# cyclo_no_flash.net
KiCad netlist of a schematic drawn in EAGLE
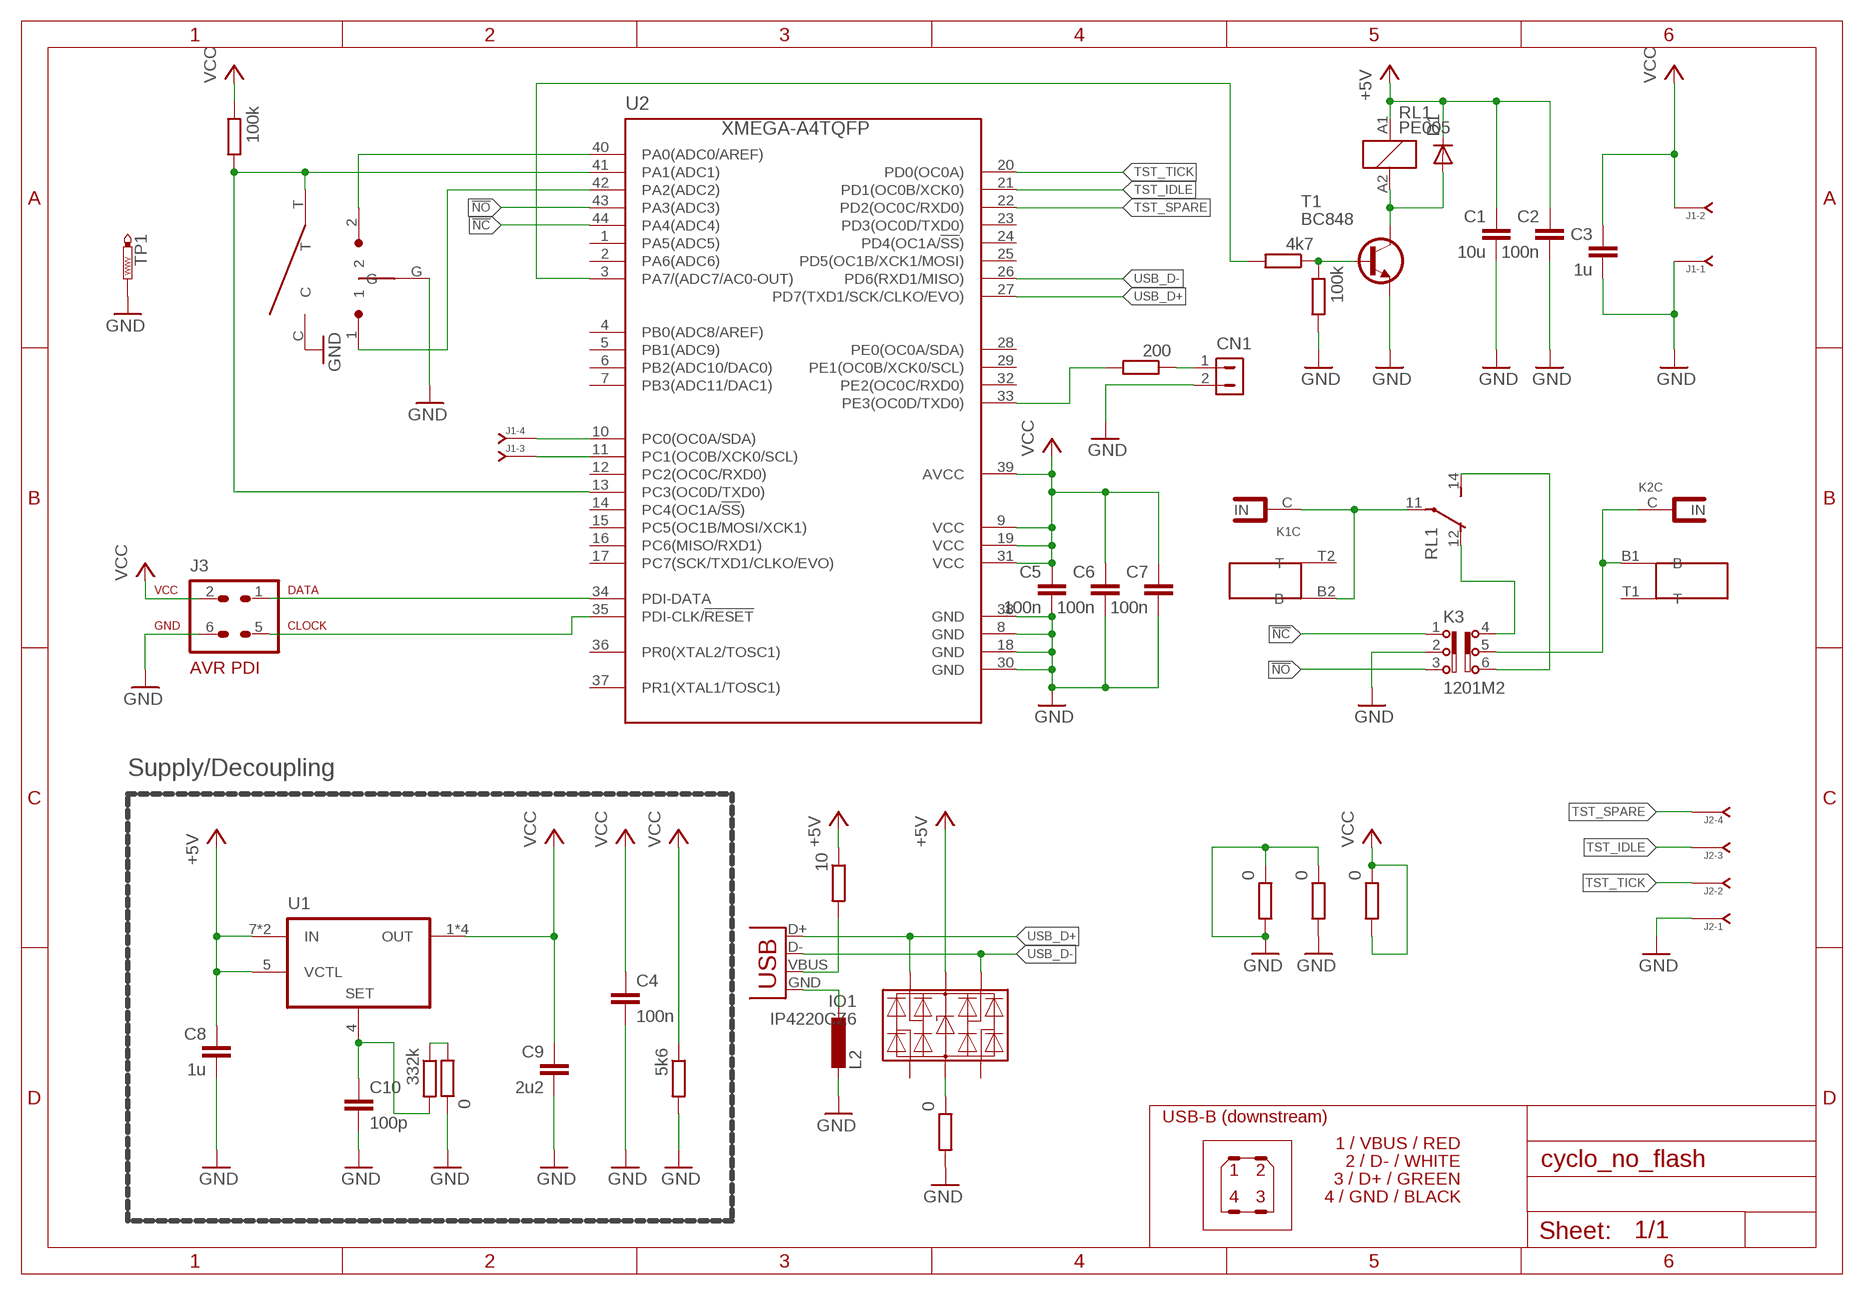
[diagram p0: schematic, sheet 1]

(export (version "E")
  (design (tool "Eeschema 10.0.6"))
  (components
    (comp (ref "C1")
      (value "10u")
      (footprint "eagle-import:C1210K")
      (libsource (lib "eagle-import") (part "C-EUC1210K"))
    )
    (comp (ref "C2")
      (value "100n")
      (footprint "eagle-import:C0603K")
      (libsource (lib "eagle-import") (part "C-EUC0603K"))
    )
    (comp (ref "C3")
      (value "1u")
      (footprint "eagle-import:C0603K")
      (libsource (lib "eagle-import") (part "C-EUC0603K"))
    )
    (comp (ref "C4")
      (value "100n")
      (footprint "eagle-import:C0603K")
      (libsource (lib "eagle-import") (part "C-EUC0603K"))
    )
    (comp (ref "C5")
      (value "100n")
      (footprint "eagle-import:C0603K")
      (libsource (lib "eagle-import") (part "C-EUC0603K"))
    )
    (comp (ref "C6")
      (value "100n")
      (footprint "eagle-import:C0603K")
      (libsource (lib "eagle-import") (part "C-EUC0603K"))
    )
    (comp (ref "C7")
      (value "100n")
      (footprint "eagle-import:C0603K")
      (libsource (lib "eagle-import") (part "C-EUC0603K"))
    )
    (comp (ref "C8")
      (value "1u")
      (footprint "eagle-import:C0805K")
      (libsource (lib "eagle-import") (part "C-EUC0805K"))
    )
    (comp (ref "C9")
      (value "2u2")
      (footprint "eagle-import:C0805K")
      (libsource (lib "eagle-import") (part "C-EUC0805K"))
    )
    (comp (ref "C10")
      (value "100p")
      (footprint "eagle-import:C0603K")
      (libsource (lib "eagle-import") (part "C-EUC0603K"))
    )
    (comp (ref "CN1")
      (value "HDR-1X2-70543-?")
      (footprint "eagle-import:70543-02")
      (libsource (lib "eagle-import") (part "HDR-1X2-70543-?"))
    )
    (comp (ref "D1")
      (value "DIODE-MINIMELF")
      (footprint "eagle-import:MINIMELF")
      (libsource (lib "eagle-import") (part "DIODE-MINIMELF"))
    )
    (comp (ref "IO1")
      (value "IP4220CZ6")
      (footprint "eagle-import:SOT23-6")
      (libsource (lib "eagle-import") (part "IP4220CZ6"))
    )
    (comp (ref "J1")
      (value "J-04-SIP-100")
      (footprint "eagle-import:SIP-100-04")
      (libsource (lib "eagle-import") (part "J-04-SIP-100"))
    )
    (comp (ref "J2")
      (value "J-04-SIP-100")
      (footprint "eagle-import:SIP-100-04")
      (libsource (lib "eagle-import") (part "J-04-SIP-100"))
    )
    (comp (ref "J3")
      (value "AVR-PDIVERT")
      (footprint "eagle-import:AVR-ISP-6")
      (libsource (lib "eagle-import") (part "AVR-PDIVERT"))
    )
    (comp (ref "K1")
      (value "S16N-PCK")
      (footprint "eagle-import:S16N-PC")
      (libsource (lib "eagle-import") (part "S16N-PCK"))
    )
    (comp (ref "K2")
      (value "S16N-PCK")
      (footprint "eagle-import:S16N-PC")
      (libsource (lib "eagle-import") (part "S16N-PCK"))
    )
    (comp (ref "K3")
      (value "1201M2")
      (footprint "eagle-import:1201M2")
      (libsource (lib "eagle-import") (part "1201M2"))
    )
    (comp (ref "L2")
      (value "L-EUL2012C")
      (footprint "eagle-import:L2012C")
      (libsource (lib "eagle-import") (part "L-EUL2012C"))
    )
    (comp (ref "R1")
      (value "4k7")
      (footprint "eagle-import:R0603")
      (libsource (lib "eagle-import") (part "R-EU_R0603"))
    )
    (comp (ref "R2")
      (value "0")
      (footprint "eagle-import:R0603")
      (libsource (lib "eagle-import") (part "R-EU_R0603"))
    )
    (comp (ref "R3")
      (value "332k")
      (footprint "eagle-import:R0603")
      (libsource (lib "eagle-import") (part "R-EU_R0603"))
    )
    (comp (ref "R4")
      (value "0")
      (footprint "eagle-import:R0603")
      (libsource (lib "eagle-import") (part "R-EU_R0603"))
    )
    (comp (ref "R5")
      (value "5k6")
      (footprint "eagle-import:R0603")
      (libsource (lib "eagle-import") (part "R-EU_R0603"))
    )
    (comp (ref "R6")
      (value "200")
      (footprint "eagle-import:R0603")
      (libsource (lib "eagle-import") (part "R-EU_R0603"))
    )
    (comp (ref "R7")
      (value "10")
      (footprint "eagle-import:R1210")
      (libsource (lib "eagle-import") (part "R-EU_R1210"))
    )
    (comp (ref "R8")
      (value "0")
      (footprint "eagle-import:R1206")
      (libsource (lib "eagle-import") (part "R-EU_R1206"))
    )
    (comp (ref "R9")
      (value "100k")
      (footprint "eagle-import:R0603")
      (libsource (lib "eagle-import") (part "R-EU_R0603"))
    )
    (comp (ref "R10")
      (value "100k")
      (footprint "eagle-import:R0603")
      (libsource (lib "eagle-import") (part "R-EU_R0603"))
    )
    (comp (ref "R11")
      (value "0")
      (footprint "eagle-import:R1206")
      (libsource (lib "eagle-import") (part "R-EU_R1206"))
    )
    (comp (ref "R12")
      (value "0")
      (footprint "eagle-import:R1206")
      (libsource (lib "eagle-import") (part "R-EU_R1206"))
    )
    (comp (ref "RL1")
      (value "PE005")
      (footprint "eagle-import:PE")
      (libsource (lib "eagle-import") (part "PE005"))
    )
    (comp (ref "T1")
      (value "BC848")
      (footprint "eagle-import:SOT23")
      (libsource (lib "eagle-import") (part "BC848"))
    )
    (comp (ref "TP1")
      (value "PTR1PAD1-17Y")
      (footprint "eagle-import:P1-17Y")
      (libsource (lib "eagle-import") (part "PTR1PAD1-17Y"))
    )
    (comp (ref "U$1")
      (value "H-MOLEX-2")
      (footprint "eagle-import:H-MOLEX2")
      (libsource (lib "eagle-import") (part "H-MOLEX-2"))
    )
    (comp (ref "U$3")
      (value "MCPL3BC-V")
      (footprint "eagle-import:MCPL3-BC-V")
      (libsource (lib "eagle-import") (part "MCPL3BC-V"))
    )
    (comp (ref "U1")
      (value "LT3085")
      (footprint "eagle-import:MS8E")
      (libsource (lib "eagle-import") (part "LT3085"))
    )
    (comp (ref "U2")
      (value "XMEGA-A4TQFP")
      (footprint "eagle-import:TQFP44")
      (libsource (lib "eagle-import") (part "XMEGA-A4TQFP"))
    )
    (comp (ref "X4")
      (value "USB-B-H")
      (footprint "eagle-import:USB-B-H")
      (libsource (lib "eagle-import") (part "USB-B-H"))
    )
  )
  (nets
    (net (code "1") (name "+5V") (class "Default")
      (node (ref "C1") (pin "1") (pinfunction "1_1") (pintype "passive"))
      (node (ref "C2") (pin "1") (pinfunction "1_1") (pintype "passive"))
      (node (ref "C8") (pin "1") (pinfunction "1_1") (pintype "passive"))
      (node (ref "D1") (pin "C") (pinfunction "C_C") (pintype "passive"))
      (node (ref "IO1") (pin "5") (pinfunction "UCC_5") (pintype "bidirectional"))
      (node (ref "R7") (pin "1") (pinfunction "1_1") (pintype "passive"))
      (node (ref "RL1") (pin "A1") (pinfunction "1_A1") (pintype "passive"))
      (node (ref "U1") (pin "5") (pinfunction "VCTL_5") (pintype "input"))
      (node (ref "U1") (pin "7") (pinfunction "IN_7") (pintype "input"))
      (node (ref "U1") (pin "8") (pinfunction "IN_8") (pintype "input"))
    )
    (net (code "2") (name "/~{NC}") (class "Default")
      (node (ref "K3") (pin "1") (pinfunction "1_1") (pintype "passive"))
      (node (ref "U2") (pin "44") (pinfunction "PA4(ADC4)_44") (pintype "bidirectional"))
    )
    (net (code "3") (name "/~{NO}") (class "Default")
      (node (ref "K3") (pin "3") (pinfunction "3_3") (pintype "passive"))
      (node (ref "U2") (pin "43") (pinfunction "PA3(ADC3)_43") (pintype "bidirectional"))
    )
    (net (code "4") (name "GND") (class "Default")
      (node (ref "C1") (pin "2") (pinfunction "2_2") (pintype "passive"))
      (node (ref "C10") (pin "2") (pinfunction "2_2") (pintype "passive"))
      (node (ref "C2") (pin "2") (pinfunction "2_2") (pintype "passive"))
      (node (ref "C3") (pin "2") (pinfunction "2_2") (pintype "passive"))
      (node (ref "C4") (pin "2") (pinfunction "2_2") (pintype "passive"))
      (node (ref "C5") (pin "2") (pinfunction "2_2") (pintype "passive"))
      (node (ref "C6") (pin "2") (pinfunction "2_2") (pintype "passive"))
      (node (ref "C7") (pin "2") (pinfunction "2_2") (pintype "passive"))
      (node (ref "C8") (pin "2") (pinfunction "2_2") (pintype "passive"))
      (node (ref "C9") (pin "2") (pinfunction "2_2") (pintype "passive"))
      (node (ref "CN1") (pin "2") (pinfunction "2_2") (pintype "passive"))
      (node (ref "J1") (pin "1") (pinfunction "J_1") (pintype "passive"))
      (node (ref "J2") (pin "1") (pinfunction "J_1") (pintype "passive"))
      (node (ref "J3") (pin "6") (pinfunction "6_6") (pintype "passive"))
      (node (ref "K3") (pin "2") (pinfunction "2_2") (pintype "passive"))
      (node (ref "L2") (pin "2") (pinfunction "2_2") (pintype "passive"))
      (node (ref "R10") (pin "2") (pinfunction "2_2") (pintype "passive"))
      (node (ref "R11") (pin "1") (pinfunction "1_1") (pintype "passive"))
      (node (ref "R11") (pin "2") (pinfunction "2_2") (pintype "passive"))
      (node (ref "R2") (pin "1") (pinfunction "1_1") (pintype "passive"))
      (node (ref "R4") (pin "2") (pinfunction "2_2") (pintype "passive"))
      (node (ref "R5") (pin "2") (pinfunction "2_2") (pintype "passive"))
      (node (ref "R8") (pin "1") (pinfunction "1_1") (pintype "passive"))
      (node (ref "R8") (pin "2") (pinfunction "2_2") (pintype "passive"))
      (node (ref "T1") (pin "2") (pinfunction "E_2") (pintype "passive"))
      (node (ref "TP1") (pin "1") (pinfunction "TP_1") (pintype "input"))
      (node (ref "U$3") (pin "C") (pinfunction "C_C") (pintype "bidirectional"))
      (node (ref "U$3") (pin "G") (pinfunction "G_G") (pintype "bidirectional"))
      (node (ref "U2") (pin "18") (pinfunction "GND_18") (pintype "power_in"))
      (node (ref "U2") (pin "30") (pinfunction "GND_30") (pintype "power_in"))
      (node (ref "U2") (pin "38") (pinfunction "GND_38") (pintype "power_in"))
      (node (ref "U2") (pin "8") (pinfunction "GND_8") (pintype "power_in"))
    )
    (net (code "5") (name "Net-(CN1-Pad1)") (class "Default")
      (node (ref "CN1") (pin "1") (pinfunction "1_1") (pintype "passive"))
      (node (ref "R6") (pin "1") (pinfunction "1_1") (pintype "passive"))
    )
    (net (code "6") (name "Net-(IO1-GND)") (class "Default")
      (node (ref "IO1") (pin "2") (pinfunction "GND_2") (pintype "bidirectional"))
      (node (ref "R4") (pin "1") (pinfunction "1_1") (pintype "passive"))
    )
    (net (code "7") (name "Net-(J1C-J)") (class "Default")
      (node (ref "J1") (pin "3") (pinfunction "J_3") (pintype "passive"))
      (node (ref "U2") (pin "11") (pinfunction "PC1(OC0B/XCK0/SCL)_11") (pintype "bidirectional"))
    )
    (net (code "8") (name "Net-(J1D-J)") (class "Default")
      (node (ref "J1") (pin "4") (pinfunction "J_4") (pintype "passive"))
      (node (ref "U2") (pin "10") (pinfunction "PC0(OC0A/SDA)_10") (pintype "bidirectional"))
    )
    (net (code "9") (name "Net-(K1E-IN)") (class "Default")
      (node (ref "K1") (pin "C") (pinfunction "IN_C") (pintype "bidirectional"))
      (node (ref "RL1") (pin "11") (pinfunction "P_11") (pintype "passive"))
      (node (ref "U$1") (pin "B2") (pinfunction "B_B2") (pintype "bidirectional"))
    )
    (net (code "10") (name "Net-(K2E-IN)") (class "Default")
      (node (ref "K2") (pin "C") (pinfunction "IN_C") (pintype "bidirectional"))
      (node (ref "K3") (pin "5") (pinfunction "5_5") (pintype "passive"))
      (node (ref "U$1") (pin "B1") (pinfunction "B_B1") (pintype "bidirectional"))
    )
    (net (code "11") (name "Net-(L2-Pad1)") (class "Default")
      (node (ref "L2") (pin "1") (pinfunction "1_1") (pintype "passive"))
      (node (ref "X4") (pin "GND") (pinfunction "GND_GND") (pintype "bidirectional"))
    )
    (net (code "12") (name "Net-(R2-Pad2)") (class "Default")
      (node (ref "R2") (pin "2") (pinfunction "2_2") (pintype "passive"))
      (node (ref "R3") (pin "1") (pinfunction "1_1") (pintype "passive"))
    )
    (net (code "13") (name "Net-(R7-Pad2)") (class "Default")
      (node (ref "R7") (pin "2") (pinfunction "2_2") (pintype "passive"))
      (node (ref "X4") (pin "VBUS") (pinfunction "VBUS_VBUS") (pintype "bidirectional"))
    )
    (net (code "14") (name "Net-(RL1A-2)") (class "Default")
      (node (ref "D1") (pin "A") (pinfunction "A_A") (pintype "passive"))
      (node (ref "RL1") (pin "A2") (pinfunction "2_A2") (pintype "passive"))
      (node (ref "T1") (pin "3") (pinfunction "C_3") (pintype "passive"))
    )
    (net (code "15") (name "Net-(RL1B-O)") (class "Default")
      (node (ref "K3") (pin "4") (pinfunction "4_4") (pintype "passive"))
      (node (ref "RL1") (pin "12") (pinfunction "O_12") (pintype "passive"))
    )
    (net (code "16") (name "Net-(RL1B-S)") (class "Default")
      (node (ref "K3") (pin "6") (pinfunction "6_6") (pintype "passive"))
      (node (ref "RL1") (pin "14") (pinfunction "S_14") (pintype "passive"))
    )
    (net (code "17") (name "Net-(T1-B)") (class "Default")
      (node (ref "R1") (pin "1") (pinfunction "1_1") (pintype "passive"))
      (node (ref "R10") (pin "1") (pinfunction "1_1") (pintype "passive"))
      (node (ref "T1") (pin "1") (pinfunction "B_1") (pintype "passive"))
    )
    (net (code "18") (name "Net-(U1-SET)") (class "Default")
      (node (ref "C10") (pin "1") (pinfunction "1_1") (pintype "passive"))
      (node (ref "R3") (pin "2") (pinfunction "2_2") (pintype "passive"))
      (node (ref "U1") (pin "4") (pinfunction "SET_4") (pintype "input"))
    )
    (net (code "19") (name "Net-(U2-PA0(ADC0{slash}AREF))") (class "Default")
      (node (ref "U$3") (pin "2") (pinfunction "2_2") (pintype "bidirectional"))
      (node (ref "U2") (pin "40") (pinfunction "PA0(ADC0/AREF)_40") (pintype "bidirectional"))
    )
    (net (code "20") (name "Net-(U2-PA1(ADC1))") (class "Default")
      (node (ref "R9") (pin "2") (pinfunction "2_2") (pintype "passive"))
      (node (ref "U$3") (pin "T") (pinfunction "T_T") (pintype "bidirectional"))
      (node (ref "U2") (pin "13") (pinfunction "PC3(OC0D/TXD0)_13") (pintype "bidirectional"))
      (node (ref "U2") (pin "41") (pinfunction "PA1(ADC1)_41") (pintype "bidirectional"))
    )
    (net (code "21") (name "Net-(U2-PA2(ADC2))") (class "Default")
      (node (ref "U$3") (pin "1") (pinfunction "1_1") (pintype "bidirectional"))
      (node (ref "U2") (pin "42") (pinfunction "PA2(ADC2)_42") (pintype "bidirectional"))
    )
    (net (code "22") (name "Net-(U2-PA7{slash}(ADC7{slash}AC0-OUT))") (class "Default")
      (node (ref "R1") (pin "2") (pinfunction "2_2") (pintype "passive"))
      (node (ref "U2") (pin "3") (pinfunction "PA7/(ADC7/AC0-OUT)_3") (pintype "bidirectional"))
    )
    (net (code "23") (name "Net-(U2-PDI-CLK{slash}~{RESET})") (class "Default")
      (node (ref "J3") (pin "5") (pinfunction "5_5") (pintype "passive"))
      (node (ref "U2") (pin "35") (pinfunction "PDI-CLK/~{RESET}_35") (pintype "input"))
    )
    (net (code "24") (name "Net-(U2-PDI-DATA)") (class "Default")
      (node (ref "J3") (pin "1") (pinfunction "1_1") (pintype "passive"))
      (node (ref "U2") (pin "34") (pinfunction "PDI-DATA_34") (pintype "bidirectional"))
    )
    (net (code "25") (name "Net-(U2-PE3(OC0D{slash}TXD0))") (class "Default")
      (node (ref "R6") (pin "2") (pinfunction "2_2") (pintype "passive"))
      (node (ref "U2") (pin "33") (pinfunction "PE3(OC0D/TXD0)_33") (pintype "bidirectional"))
    )
    (net (code "26") (name "TST_IDLE") (class "Default")
      (node (ref "J2") (pin "3") (pinfunction "J_3") (pintype "passive"))
      (node (ref "U2") (pin "21") (pinfunction "PD1(OC0B/XCK0)_21") (pintype "bidirectional"))
    )
    (net (code "27") (name "TST_SPARE") (class "Default")
      (node (ref "J2") (pin "4") (pinfunction "J_4") (pintype "passive"))
      (node (ref "U2") (pin "22") (pinfunction "PD2(OC0C/RXD0)_22") (pintype "bidirectional"))
    )
    (net (code "28") (name "TST_TICK") (class "Default")
      (node (ref "J2") (pin "2") (pinfunction "J_2") (pintype "passive"))
      (node (ref "U2") (pin "20") (pinfunction "PD0(OC0A)_20") (pintype "bidirectional"))
    )
    (net (code "29") (name "USB_D+") (class "Default")
      (node (ref "IO1") (pin "3") (pinfunction "B_3") (pintype "bidirectional"))
      (node (ref "U2") (pin "27") (pinfunction "PD7(TXD1/SCK/CLKO/EVO)_27") (pintype "bidirectional"))
      (node (ref "X4") (pin "D+") (pinfunction "D+_D+") (pintype "bidirectional"))
    )
    (net (code "30") (name "USB_D-") (class "Default")
      (node (ref "IO1") (pin "1") (pinfunction "A_1") (pintype "bidirectional"))
      (node (ref "U2") (pin "26") (pinfunction "PD6(RXD1/MISO)_26") (pintype "bidirectional"))
      (node (ref "X4") (pin "D-") (pinfunction "D-_D-") (pintype "bidirectional"))
    )
    (net (code "31") (name "VCC") (class "Default")
      (node (ref "C3") (pin "1") (pinfunction "1_1") (pintype "passive"))
      (node (ref "C4") (pin "1") (pinfunction "1_1") (pintype "passive"))
      (node (ref "C5") (pin "1") (pinfunction "1_1") (pintype "passive"))
      (node (ref "C6") (pin "1") (pinfunction "1_1") (pintype "passive"))
      (node (ref "C7") (pin "1") (pinfunction "1_1") (pintype "passive"))
      (node (ref "C9") (pin "1") (pinfunction "1_1") (pintype "passive"))
      (node (ref "J1") (pin "2") (pinfunction "J_2") (pintype "passive"))
      (node (ref "J3") (pin "2") (pinfunction "2_2") (pintype "passive"))
      (node (ref "R12") (pin "1") (pinfunction "1_1") (pintype "passive"))
      (node (ref "R12") (pin "2") (pinfunction "2_2") (pintype "passive"))
      (node (ref "R5") (pin "1") (pinfunction "1_1") (pintype "passive"))
      (node (ref "R9") (pin "1") (pinfunction "1_1") (pintype "passive"))
      (node (ref "U1") (pin "1") (pinfunction "OUT_1") (pintype "passive"))
      (node (ref "U1") (pin "2") (pinfunction "OUT_2") (pintype "passive"))
      (node (ref "U1") (pin "3") (pinfunction "OUT_3") (pintype "passive"))
      (node (ref "U1") (pin "9") (pinfunction "OUT_9") (pintype "passive"))
      (node (ref "U2") (pin "19") (pinfunction "VCC_19") (pintype "power_in"))
      (node (ref "U2") (pin "31") (pinfunction "VCC_31") (pintype "power_in"))
      (node (ref "U2") (pin "39") (pinfunction "AVCC_39") (pintype "power_in"))
      (node (ref "U2") (pin "9") (pinfunction "VCC_9") (pintype "power_in"))
    )
    (net (code "32") (name "unconnected-(IO1-C-Pad4)") (class "Default")
      (node (ref "IO1") (pin "4") (pinfunction "C_4") (pintype "bidirectional"))
    )
    (net (code "33") (name "unconnected-(IO1-D-Pad6)") (class "Default")
      (node (ref "IO1") (pin "6") (pinfunction "D_6") (pintype "bidirectional"))
    )
    (net (code "34") (name "unconnected-(U$1A-T-PadT1)") (class "Default")
      (node (ref "U$1") (pin "T1") (pinfunction "T_T1") (pintype "bidirectional"))
    )
    (net (code "35") (name "unconnected-(U$1B-T-PadT2)") (class "Default")
      (node (ref "U$1") (pin "T2") (pinfunction "T_T2") (pintype "bidirectional"))
    )
    (net (code "36") (name "unconnected-(U2-PA5(ADC5)-Pad1)") (class "Default")
      (node (ref "U2") (pin "1") (pinfunction "PA5(ADC5)_1") (pintype "bidirectional"))
    )
    (net (code "37") (name "unconnected-(U2-PA6(ADC6)-Pad2)") (class "Default")
      (node (ref "U2") (pin "2") (pinfunction "PA6(ADC6)_2") (pintype "bidirectional"))
    )
    (net (code "38") (name "unconnected-(U2-PB0(ADC8{slash}AREF)-Pad4)") (class "Default")
      (node (ref "U2") (pin "4") (pinfunction "PB0(ADC8/AREF)_4") (pintype "bidirectional"))
    )
    (net (code "39") (name "unconnected-(U2-PB1(ADC9)-Pad5)") (class "Default")
      (node (ref "U2") (pin "5") (pinfunction "PB1(ADC9)_5") (pintype "bidirectional"))
    )
    (net (code "40") (name "unconnected-(U2-PB2(ADC10{slash}DAC0)-Pad6)") (class "Default")
      (node (ref "U2") (pin "6") (pinfunction "PB2(ADC10/DAC0)_6") (pintype "bidirectional"))
    )
    (net (code "41") (name "unconnected-(U2-PB3(ADC11{slash}DAC1)-Pad7)") (class "Default")
      (node (ref "U2") (pin "7") (pinfunction "PB3(ADC11/DAC1)_7") (pintype "bidirectional"))
    )
    (net (code "42") (name "unconnected-(U2-PC2(OC0C{slash}RXD0)-Pad12)") (class "Default")
      (node (ref "U2") (pin "12") (pinfunction "PC2(OC0C/RXD0)_12") (pintype "bidirectional"))
    )
    (net (code "43") (name "unconnected-(U2-PC4(OC1A{slash}~{SS})-Pad14)") (class "Default")
      (node (ref "U2") (pin "14") (pinfunction "PC4(OC1A/~{SS})_14") (pintype "bidirectional"))
    )
    (net (code "44") (name "unconnected-(U2-PC5(OC1B{slash}MOSI{slash}XCK1)-Pad15)") (class "Default")
      (node (ref "U2") (pin "15") (pinfunction "PC5(OC1B/MOSI/XCK1)_15") (pintype "bidirectional"))
    )
    (net (code "45") (name "unconnected-(U2-PC6(MISO{slash}RXD1)-Pad16)") (class "Default")
      (node (ref "U2") (pin "16") (pinfunction "PC6(MISO/RXD1)_16") (pintype "bidirectional"))
    )
    (net (code "46") (name "unconnected-(U2-PC7(SCK{slash}TXD1{slash}CLKO{slash}EVO)-Pad17)") (class "Default")
      (node (ref "U2") (pin "17") (pinfunction "PC7(SCK/TXD1/CLKO/EVO)_17") (pintype "bidirectional"))
    )
    (net (code "47") (name "unconnected-(U2-PD3(OC0D{slash}TXD0)-Pad23)") (class "Default")
      (node (ref "U2") (pin "23") (pinfunction "PD3(OC0D/TXD0)_23") (pintype "bidirectional"))
    )
    (net (code "48") (name "unconnected-(U2-PD4(OC1A{slash}~{SS})-Pad24)") (class "Default")
      (node (ref "U2") (pin "24") (pinfunction "PD4(OC1A/~{SS})_24") (pintype "bidirectional"))
    )
    (net (code "49") (name "unconnected-(U2-PD5(OC1B{slash}XCK1{slash}MOSI)-Pad25)") (class "Default")
      (node (ref "U2") (pin "25") (pinfunction "PD5(OC1B/XCK1/MOSI)_25") (pintype "bidirectional"))
    )
    (net (code "50") (name "unconnected-(U2-PE0(OC0A{slash}SDA)-Pad28)") (class "Default")
      (node (ref "U2") (pin "28") (pinfunction "PE0(OC0A/SDA)_28") (pintype "bidirectional"))
    )
    (net (code "51") (name "unconnected-(U2-PE1(OC0B{slash}XCK0{slash}SCL)-Pad29)") (class "Default")
      (node (ref "U2") (pin "29") (pinfunction "PE1(OC0B/XCK0/SCL)_29") (pintype "bidirectional"))
    )
    (net (code "52") (name "unconnected-(U2-PE2(OC0C{slash}RXD0)-Pad32)") (class "Default")
      (node (ref "U2") (pin "32") (pinfunction "PE2(OC0C/RXD0)_32") (pintype "bidirectional"))
    )
    (net (code "53") (name "unconnected-(U2-PR0(XTAL2{slash}TOSC1)-Pad36)") (class "Default")
      (node (ref "U2") (pin "36") (pinfunction "PR0(XTAL2/TOSC1)_36") (pintype "bidirectional"))
    )
    (net (code "54") (name "unconnected-(U2-PR1(XTAL1{slash}TOSC1)-Pad37)") (class "Default")
      (node (ref "U2") (pin "37") (pinfunction "PR1(XTAL1/TOSC1)_37") (pintype "bidirectional"))
    )
  )
)
